# Charger_status_detector.net
KiCad netlist of a schematic drawn in EAGLE
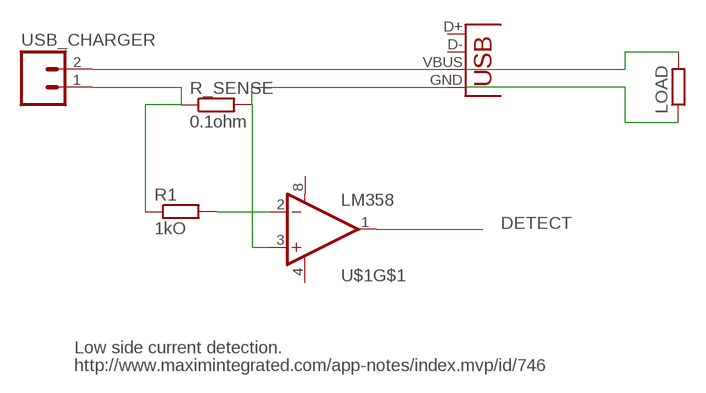
[diagram p0: schematic, sheet 1]

(export (version "E")
  (design (tool "Eeschema 10.0.6"))
  (components
    (comp (ref "JP1")
      (value "USBOLD")
      (footprint "eagle-import:USB-MINIB-OLD")
      (libsource (lib "eagle-import") (part "USBOLD"))
    )
    (comp (ref "LOAD")
      (value "R-EU_0207/10")
      (footprint "eagle-import:0207_10")
      (libsource (lib "eagle-import") (part "R-EU_0207/10"))
    )
    (comp (ref "R1")
      (value "1kO")
      (footprint "eagle-import:0207_10")
      (libsource (lib "eagle-import") (part "R-EU_0207/10"))
    )
    (comp (ref "R_SENSE")
      (value "0.1ohm")
      (footprint "eagle-import:0207_10")
      (libsource (lib "eagle-import") (part "R-EU_0207/10"))
    )
    (comp (ref "U$1")
      (value "LM358")
      (footprint "eagle-import:DIP08")
      (libsource (lib "eagle-import") (part "LM358"))
    )
    (comp (ref "USB_CHARGER")
      (value "M02LOCK")
      (footprint "eagle-import:1X02_LOCK")
      (libsource (lib "eagle-import") (part "M02LOCK"))
    )
  )
  (nets
    (net (code "1") (name "/DETECT") (class "Default")
      (node (ref "U$1") (pin "1") (pinfunction "OUT_1") (pintype "output"))
    )
    (net (code "2") (name "/V+") (class "Default")
      (node (ref "U$1") (pin "8") (pinfunction "V+_8") (pintype "power_in"))
    )
    (net (code "3") (name "/V-") (class "Default")
      (node (ref "U$1") (pin "4") (pinfunction "V-_4") (pintype "power_in"))
    )
    (net (code "4") (name "Net-(JP1-PadVBUS)") (class "Default")
      (node (ref "JP1") (pin "VBUS") (pinfunction "VBUS_VBUS") (pintype "bidirectional"))
      (node (ref "USB_CHARGER") (pin "2") (pinfunction "2_2") (pintype "passive"))
    )
    (net (code "5") (name "Net-(R1-Pad1)") (class "Default")
      (node (ref "R1") (pin "1") (pinfunction "1_1") (pintype "passive"))
      (node (ref "R_SENSE") (pin "1") (pinfunction "1_1") (pintype "passive"))
      (node (ref "USB_CHARGER") (pin "1") (pinfunction "1_1") (pintype "passive"))
    )
    (net (code "6") (name "Net-(U$1A-+IN)") (class "Default")
      (node (ref "JP1") (pin "GND") (pinfunction "GND_GND") (pintype "bidirectional"))
      (node (ref "R_SENSE") (pin "2") (pinfunction "2_2") (pintype "passive"))
      (node (ref "U$1") (pin "3") (pinfunction "+IN_3") (pintype "input"))
    )
    (net (code "7") (name "Net-(U$1A--IN)") (class "Default")
      (node (ref "R1") (pin "2") (pinfunction "2_2") (pintype "passive"))
      (node (ref "U$1") (pin "2") (pinfunction "-IN_2") (pintype "input"))
    )
    (net (code "8") (name "unconnected-(JP1-PadD+)") (class "Default")
      (node (ref "JP1") (pin "D+") (pinfunction "D+_D+") (pintype "bidirectional"))
    )
    (net (code "9") (name "unconnected-(JP1-PadD-)") (class "Default")
      (node (ref "JP1") (pin "D-") (pinfunction "D-_D-") (pintype "bidirectional"))
    )
    (net (code "10") (name "unconnected-(LOAD-Pad1)") (class "Default")
      (node (ref "LOAD") (pin "1") (pinfunction "1_1") (pintype "passive"))
    )
    (net (code "11") (name "unconnected-(LOAD-Pad2)") (class "Default")
      (node (ref "LOAD") (pin "2") (pinfunction "2_2") (pintype "passive"))
    )
  )
)
